# Hyundai_giraffe.net
KiCad netlist of a schematic drawn in EAGLE
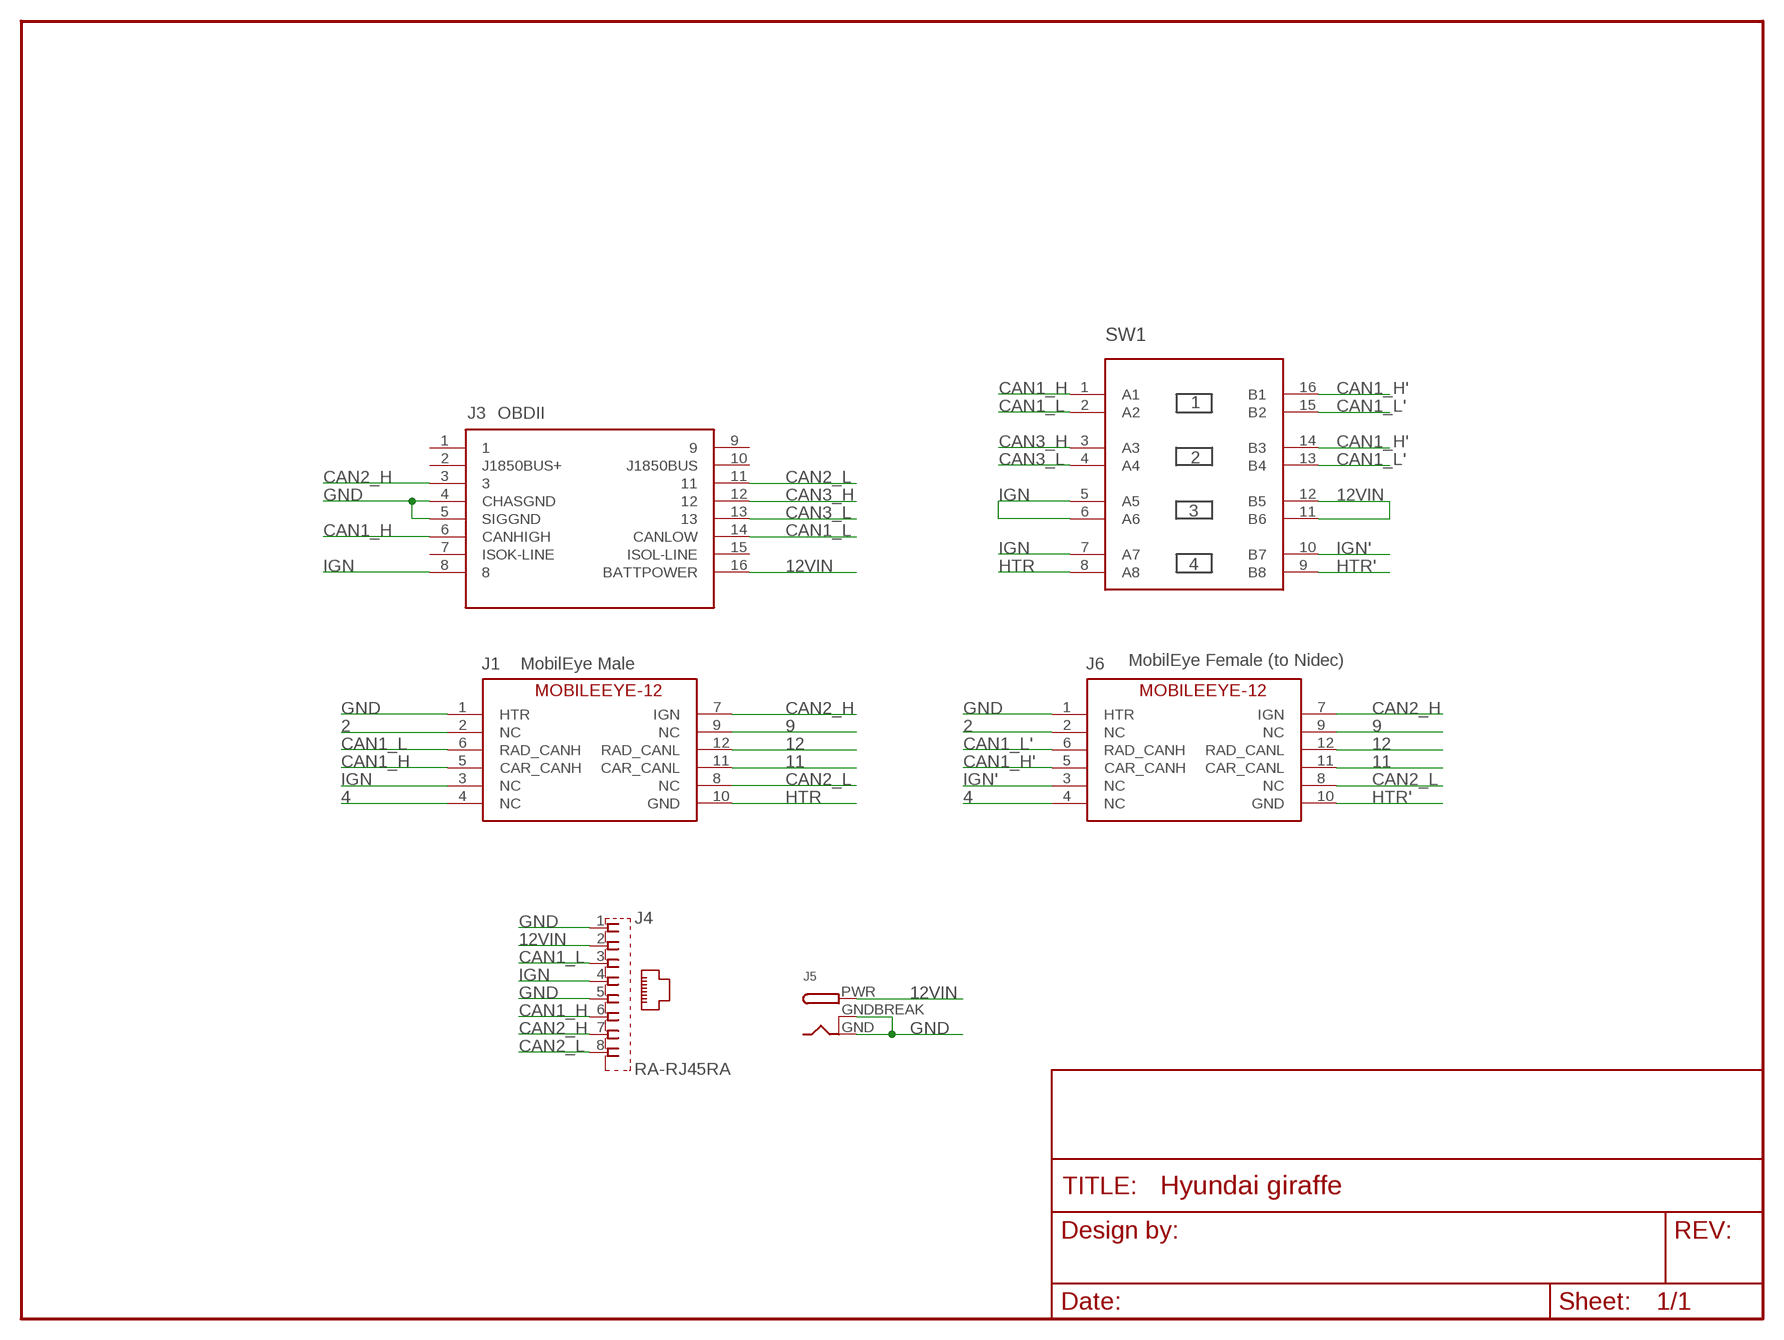
[diagram p0: schematic, sheet 1]

(export (version "E")
  (design (tool "Eeschema 10.0.6"))
  (components
    (comp (ref "FRAME1")
      (value "FRAME-LETTERNO_PACKAGE")
      (footprint "eagle-import:DUMMY")
      (fields (field (name "DESIGNER") "Nobody"))
      (libsource (lib "eagle-import") (part "FRAME-LETTERNO_PACKAGE"))
    )
    (comp (ref "J1")
      (value "COMMA.AI_MOBILEEYE-12NEW")
      (footprint "eagle-import:COMMA.AI_2X6-TE-RA_NEW")
      (libsource (lib "eagle-import") (part "COMMA.AI_MOBILEEYE-12NEW"))
    )
    (comp (ref "J3")
      (value "OBDII-FEMALE-CUT")
      (footprint "eagle-import:OBDII-FEMALE-MIDCUT")
      (libsource (lib "eagle-import") (part "OBDII-FEMALE-CUT"))
    )
    (comp (ref "J4")
      (value "RA-RJ45RA")
      (footprint "eagle-import:RA-RJ45")
      (libsource (lib "eagle-import") (part "RA-RJ45RA"))
    )
    (comp (ref "J5")
      (value "DCBARRELPTH")
      (footprint "eagle-import:DCJACK_2MM_PTH")
      (libsource (lib "eagle-import") (part "DCBARRELPTH"))
    )
    (comp (ref "J6")
      (value "COMMA.AI_MOBILEEYE-12")
      (footprint "eagle-import:COMMA.AI_2X6-TE-FEMALE_NEW")
      (libsource (lib "eagle-import") (part "COMMA.AI_MOBILEEYE-12"))
    )
    (comp (ref "SW1")
      (value "4XDPSTSMT")
      (footprint "eagle-import:4-DPST")
      (libsource (lib "eagle-import") (part "4XDPSTSMT"))
    )
  )
  (nets
    (net (code "1") (name "/2") (class "Default")
      (node (ref "J1") (pin "2") (pinfunction "NC_2") (pintype "bidirectional"))
      (node (ref "J6") (pin "2") (pinfunction "NC_2") (pintype "bidirectional"))
    )
    (net (code "2") (name "/4") (class "Default")
      (node (ref "J1") (pin "4") (pinfunction "NC_4") (pintype "bidirectional"))
      (node (ref "J6") (pin "4") (pinfunction "NC_4") (pintype "bidirectional"))
    )
    (net (code "3") (name "/9") (class "Default")
      (node (ref "J1") (pin "9") (pinfunction "NC_9") (pintype "bidirectional"))
      (node (ref "J6") (pin "9") (pinfunction "NC_9") (pintype "bidirectional"))
    )
    (net (code "4") (name "/11") (class "Default")
      (node (ref "J1") (pin "11") (pinfunction "CAR_CANL_11") (pintype "bidirectional"))
      (node (ref "J6") (pin "11") (pinfunction "CAR_CANL_11") (pintype "bidirectional"))
    )
    (net (code "5") (name "/12") (class "Default")
      (node (ref "J1") (pin "12") (pinfunction "RAD_CANL_12") (pintype "bidirectional"))
      (node (ref "J6") (pin "12") (pinfunction "RAD_CANL_12") (pintype "bidirectional"))
    )
    (net (code "6") (name "/12VIN") (class "Default")
      (node (ref "J3") (pin "16") (pinfunction "BATTPOWER_16") (pintype "bidirectional"))
      (node (ref "J4") (pin "2") (pinfunction "2_2") (pintype "passive"))
      (node (ref "J5") (pin "PWR") (pinfunction "PWR_PWR") (pintype "power_in"))
      (node (ref "SW1") (pin "11") (pinfunction "B6_11") (pintype "bidirectional"))
      (node (ref "SW1") (pin "12") (pinfunction "B5_12") (pintype "bidirectional"))
    )
    (net (code "7") (name "/CAN1_H") (class "Default")
      (node (ref "J1") (pin "5") (pinfunction "CAR_CANH_5") (pintype "bidirectional"))
      (node (ref "J3") (pin "6") (pinfunction "CANHIGH_6") (pintype "bidirectional"))
      (node (ref "J4") (pin "6") (pinfunction "6_6") (pintype "passive"))
      (node (ref "SW1") (pin "1") (pinfunction "A1_1") (pintype "bidirectional"))
    )
    (net (code "8") (name "/CAN1_H'") (class "Default")
      (node (ref "J6") (pin "5") (pinfunction "CAR_CANH_5") (pintype "bidirectional"))
      (node (ref "SW1") (pin "14") (pinfunction "B3_14") (pintype "bidirectional"))
      (node (ref "SW1") (pin "16") (pinfunction "B1_16") (pintype "bidirectional"))
    )
    (net (code "9") (name "/CAN1_L") (class "Default")
      (node (ref "J1") (pin "6") (pinfunction "RAD_CANH_6") (pintype "bidirectional"))
      (node (ref "J3") (pin "14") (pinfunction "CANLOW_14") (pintype "bidirectional"))
      (node (ref "J4") (pin "3") (pinfunction "3_3") (pintype "passive"))
      (node (ref "SW1") (pin "2") (pinfunction "A2_2") (pintype "bidirectional"))
    )
    (net (code "10") (name "/CAN1_L'") (class "Default")
      (node (ref "J6") (pin "6") (pinfunction "RAD_CANH_6") (pintype "bidirectional"))
      (node (ref "SW1") (pin "13") (pinfunction "B4_13") (pintype "bidirectional"))
      (node (ref "SW1") (pin "15") (pinfunction "B2_15") (pintype "bidirectional"))
    )
    (net (code "11") (name "/CAN2_H") (class "Default")
      (node (ref "J1") (pin "7") (pinfunction "IGN_7") (pintype "bidirectional"))
      (node (ref "J3") (pin "3") (pinfunction "3_3") (pintype "bidirectional"))
      (node (ref "J4") (pin "7") (pinfunction "7_7") (pintype "passive"))
      (node (ref "J6") (pin "7") (pinfunction "IGN_7") (pintype "bidirectional"))
    )
    (net (code "12") (name "/CAN2_L") (class "Default")
      (node (ref "J1") (pin "8") (pinfunction "NC_8") (pintype "bidirectional"))
      (node (ref "J3") (pin "11") (pinfunction "11_11") (pintype "bidirectional"))
      (node (ref "J4") (pin "8") (pinfunction "8_8") (pintype "passive"))
      (node (ref "J6") (pin "8") (pinfunction "NC_8") (pintype "bidirectional"))
    )
    (net (code "13") (name "/CAN3_H") (class "Default")
      (node (ref "J3") (pin "12") (pinfunction "12_12") (pintype "bidirectional"))
      (node (ref "SW1") (pin "3") (pinfunction "A3_3") (pintype "bidirectional"))
    )
    (net (code "14") (name "/CAN3_L") (class "Default")
      (node (ref "J3") (pin "13") (pinfunction "13_13") (pintype "bidirectional"))
      (node (ref "SW1") (pin "4") (pinfunction "A4_4") (pintype "bidirectional"))
    )
    (net (code "15") (name "/GND") (class "Default")
      (node (ref "J1") (pin "1") (pinfunction "HTR_1") (pintype "bidirectional"))
      (node (ref "J3") (pin "4") (pinfunction "CHASGND_4") (pintype "bidirectional"))
      (node (ref "J3") (pin "5") (pinfunction "SIGGND_5") (pintype "bidirectional"))
      (node (ref "J4") (pin "1") (pinfunction "1_1") (pintype "passive"))
      (node (ref "J4") (pin "5") (pinfunction "5_5") (pintype "passive"))
      (node (ref "J5") (pin "GND") (pinfunction "GND_GND") (pintype "power_in"))
      (node (ref "J5") (pin "GNDBREAK") (pinfunction "GNDBREAK_GNDBREAK") (pintype "power_in"))
      (node (ref "J6") (pin "1") (pinfunction "HTR_1") (pintype "bidirectional"))
    )
    (net (code "16") (name "/HTR") (class "Default")
      (node (ref "J1") (pin "10") (pinfunction "GND_10") (pintype "bidirectional"))
      (node (ref "SW1") (pin "8") (pinfunction "A8_8") (pintype "bidirectional"))
    )
    (net (code "17") (name "/HTR'") (class "Default")
      (node (ref "J6") (pin "10") (pinfunction "GND_10") (pintype "bidirectional"))
      (node (ref "SW1") (pin "9") (pinfunction "B8_9") (pintype "bidirectional"))
    )
    (net (code "18") (name "/IGN") (class "Default")
      (node (ref "J1") (pin "3") (pinfunction "NC_3") (pintype "bidirectional"))
      (node (ref "J3") (pin "8") (pinfunction "8_8") (pintype "bidirectional"))
      (node (ref "J4") (pin "4") (pinfunction "4_4") (pintype "passive"))
      (node (ref "SW1") (pin "5") (pinfunction "A5_5") (pintype "bidirectional"))
      (node (ref "SW1") (pin "6") (pinfunction "A6_6") (pintype "bidirectional"))
      (node (ref "SW1") (pin "7") (pinfunction "A7_7") (pintype "bidirectional"))
    )
    (net (code "19") (name "/IGN'") (class "Default")
      (node (ref "J6") (pin "3") (pinfunction "NC_3") (pintype "bidirectional"))
      (node (ref "SW1") (pin "10") (pinfunction "B7_10") (pintype "bidirectional"))
    )
    (net (code "20") (name "unconnected-(J3-ISOK-LINE-Pad7)") (class "Default")
      (node (ref "J3") (pin "7") (pinfunction "ISOK-LINE_7") (pintype "bidirectional"))
    )
    (net (code "21") (name "unconnected-(J3-ISOL-LINE-Pad15)") (class "Default")
      (node (ref "J3") (pin "15") (pinfunction "ISOL-LINE_15") (pintype "bidirectional"))
    )
    (net (code "22") (name "unconnected-(J3-J1850BUS+-Pad2)") (class "Default")
      (node (ref "J3") (pin "2") (pinfunction "J1850BUS+_2") (pintype "bidirectional"))
    )
    (net (code "23") (name "unconnected-(J3-J1850BUS-Pad10)") (class "Default")
      (node (ref "J3") (pin "10") (pinfunction "J1850BUS_10") (pintype "bidirectional"))
    )
    (net (code "24") (name "unconnected-(J3-Pad1)") (class "Default")
      (node (ref "J3") (pin "1") (pinfunction "1_1") (pintype "bidirectional"))
    )
    (net (code "25") (name "unconnected-(J3-Pad9)") (class "Default")
      (node (ref "J3") (pin "9") (pinfunction "9_9") (pintype "bidirectional"))
    )
  )
)
